# sd.net
KiCad netlist of a schematic drawn in Altium Designer
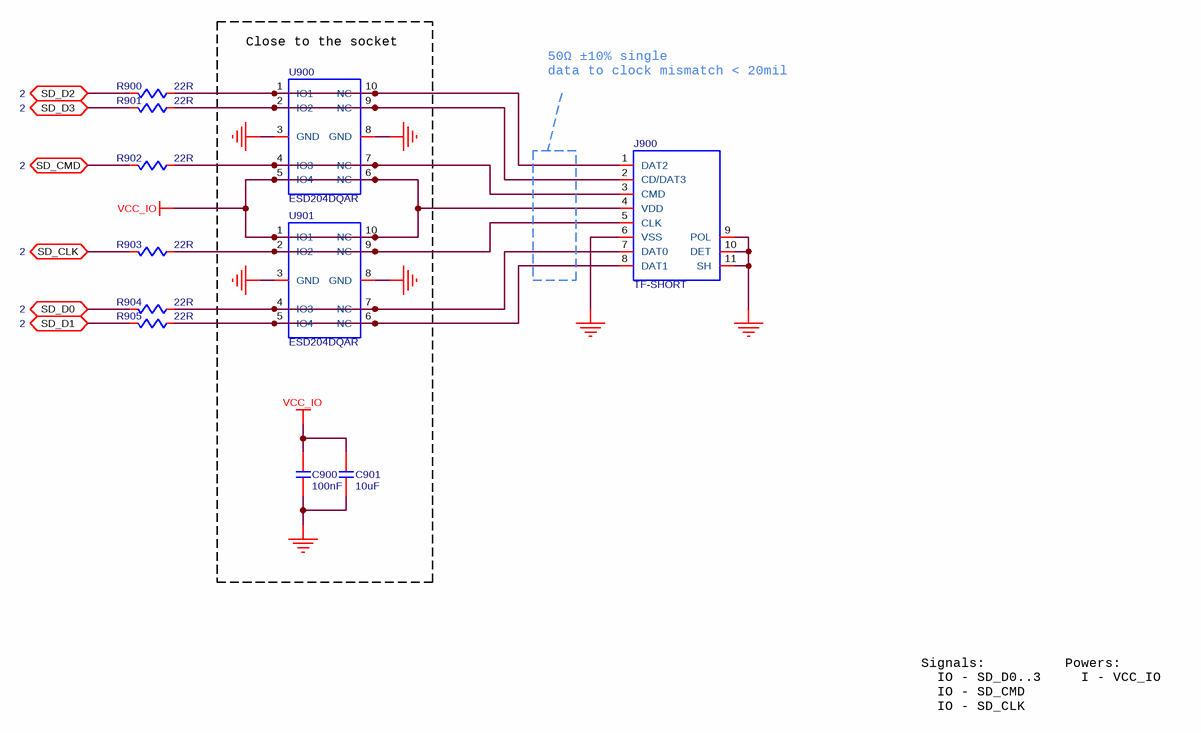
[diagram p0: sd.schdoc]

(export (version "E")
  (design (tool "Eeschema 10.0.6"))
  (components
    (comp (ref "C900")
      (value "100nF")
      (footprint "mw:C0402")
      (fields (field (name "VOLTAGE") "50V") (field (name "Comment") "C-NOMO"))
      (libsource (lib "mw") (part "C-NOMO"))
    )
    (comp (ref "C901")
      (value "10uF")
      (footprint "mw:C0402")
      (fields (field (name "VOLTAGE") "6.3V") (field (name "Comment") "C-NOMO"))
      (libsource (lib "mw") (part "C-NOMO"))
    )
    (comp (ref "J900")
      (value "TF-SHORT")
      (footprint "mw:TF-SHORT")
      (description "SOCKET - MicroSD socket with detction")
      (libsource (lib "mw") (part "TF-SHORT"))
    )
    (comp (ref "R900")
      (value "22R")
      (footprint "mw:R0402")
      (fields (field (name "Comment") "R"))
      (libsource (lib "mw") (part "R"))
    )
    (comp (ref "R901")
      (value "22R")
      (footprint "mw:R0402")
      (fields (field (name "Comment") "R"))
      (libsource (lib "mw") (part "R"))
    )
    (comp (ref "R902")
      (value "22R")
      (footprint "mw:R0402")
      (fields (field (name "Comment") "R"))
      (libsource (lib "mw") (part "R"))
    )
    (comp (ref "R903")
      (value "22R")
      (footprint "mw:R0402")
      (fields (field (name "Comment") "R"))
      (libsource (lib "mw") (part "R"))
    )
    (comp (ref "R904")
      (value "22R")
      (footprint "mw:R0402")
      (fields (field (name "Comment") "R"))
      (libsource (lib "mw") (part "R"))
    )
    (comp (ref "R905")
      (value "22R")
      (footprint "mw:R0402")
      (fields (field (name "Comment") "R"))
      (libsource (lib "mw") (part "R"))
    )
    (comp (ref "U900")
      (value "ESD204DQAR")
      (footprint "mw:ESD204DQAR")
      (description "TVS/ESD - 4 ch, 3.6V, 5V, 0.55pF@1MHz, 30KV")
      (libsource (lib "mw") (part "ESD204DQAR"))
    )
    (comp (ref "U901")
      (value "ESD204DQAR")
      (footprint "mw:ESD204DQAR")
      (description "TVS/ESD - 4 ch, 3.6V, 5V, 0.55pF@1MHz, 30KV")
      (libsource (lib "mw") (part "ESD204DQAR"))
    )
  )
  (nets
    (net (code "1") (name "/SD_CLK") (class "Default")
      (node (ref "R903") (pin "1") (pinfunction "1_1") (pintype "passive"))
    )
    (net (code "2") (name "/SD_CMD") (class "Default")
      (node (ref "R902") (pin "1") (pinfunction "1_1") (pintype "passive"))
    )
    (net (code "3") (name "/SD_D0") (class "Default")
      (node (ref "R904") (pin "1") (pinfunction "1_1") (pintype "passive"))
    )
    (net (code "4") (name "/SD_D1") (class "Default")
      (node (ref "R905") (pin "1") (pinfunction "1_1") (pintype "passive"))
    )
    (net (code "5") (name "/SD_D2") (class "Default")
      (node (ref "R900") (pin "1") (pinfunction "1_1") (pintype "passive"))
    )
    (net (code "6") (name "/SD_D3") (class "Default")
      (node (ref "R901") (pin "1") (pinfunction "1_1") (pintype "passive"))
    )
    (net (code "7") (name "GND") (class "Default")
      (node (ref "C900") (pin "2") (pinfunction "2_2") (pintype "passive"))
      (node (ref "C901") (pin "2") (pinfunction "2_2") (pintype "passive"))
      (node (ref "J900") (pin "10") (pinfunction "DET_10") (pintype "passive"))
      (node (ref "J900") (pin "11") (pinfunction "SH_11") (pintype "passive"))
      (node (ref "J900") (pin "6") (pinfunction "VSS_6") (pintype "passive"))
      (node (ref "J900") (pin "9") (pinfunction "POL_9") (pintype "passive"))
      (node (ref "U900") (pin "3") (pinfunction "GND_3") (pintype "passive"))
      (node (ref "U900") (pin "8") (pinfunction "GND_8") (pintype "passive"))
      (node (ref "U901") (pin "3") (pinfunction "GND_3") (pintype "passive"))
      (node (ref "U901") (pin "8") (pinfunction "GND_8") (pintype "passive"))
    )
    (net (code "8") (name "Net-(J900-CD{slash}DAT3)") (class "Default")
      (node (ref "J900") (pin "2") (pinfunction "CD/DAT3_2") (pintype "passive"))
      (node (ref "R901") (pin "2") (pinfunction "2_2") (pintype "passive"))
      (node (ref "U900") (pin "2") (pinfunction "IO2_2") (pintype "passive"))
      (node (ref "U900") (pin "9") (pinfunction "NC_9") (pintype "passive"))
    )
    (net (code "9") (name "Net-(J900-CLK)") (class "Default")
      (node (ref "J900") (pin "5") (pinfunction "CLK_5") (pintype "passive"))
      (node (ref "R903") (pin "2") (pinfunction "2_2") (pintype "passive"))
      (node (ref "U901") (pin "2") (pinfunction "IO2_2") (pintype "passive"))
      (node (ref "U901") (pin "9") (pinfunction "NC_9") (pintype "passive"))
    )
    (net (code "10") (name "Net-(J900-CMD)") (class "Default")
      (node (ref "J900") (pin "3") (pinfunction "CMD_3") (pintype "passive"))
      (node (ref "R902") (pin "2") (pinfunction "2_2") (pintype "passive"))
      (node (ref "U900") (pin "4") (pinfunction "IO3_4") (pintype "passive"))
      (node (ref "U900") (pin "7") (pinfunction "NC_7") (pintype "passive"))
    )
    (net (code "11") (name "Net-(J900-DAT0)") (class "Default")
      (node (ref "J900") (pin "7") (pinfunction "DAT0_7") (pintype "passive"))
      (node (ref "R904") (pin "2") (pinfunction "2_2") (pintype "passive"))
      (node (ref "U901") (pin "4") (pinfunction "IO3_4") (pintype "passive"))
      (node (ref "U901") (pin "7") (pinfunction "NC_7") (pintype "passive"))
    )
    (net (code "12") (name "Net-(J900-DAT1)") (class "Default")
      (node (ref "J900") (pin "8") (pinfunction "DAT1_8") (pintype "passive"))
      (node (ref "R905") (pin "2") (pinfunction "2_2") (pintype "passive"))
      (node (ref "U901") (pin "5") (pinfunction "IO4_5") (pintype "passive"))
      (node (ref "U901") (pin "6") (pinfunction "NC_6") (pintype "passive"))
    )
    (net (code "13") (name "Net-(J900-DAT2)") (class "Default")
      (node (ref "J900") (pin "1") (pinfunction "DAT2_1") (pintype "passive"))
      (node (ref "R900") (pin "2") (pinfunction "2_2") (pintype "passive"))
      (node (ref "U900") (pin "1") (pinfunction "IO1_1") (pintype "passive"))
      (node (ref "U900") (pin "10") (pinfunction "NC_10") (pintype "passive"))
    )
    (net (code "14") (name "VCC_IO") (class "Default")
      (node (ref "C900") (pin "1") (pinfunction "1_1") (pintype "passive"))
      (node (ref "C901") (pin "1") (pinfunction "1_1") (pintype "passive"))
      (node (ref "J900") (pin "4") (pinfunction "VDD_4") (pintype "passive"))
      (node (ref "U900") (pin "5") (pinfunction "IO4_5") (pintype "passive"))
      (node (ref "U900") (pin "6") (pinfunction "NC_6") (pintype "passive"))
      (node (ref "U901") (pin "1") (pinfunction "IO1_1") (pintype "passive"))
      (node (ref "U901") (pin "10") (pinfunction "NC_10") (pintype "passive"))
    )
  )
)
